# Debug_IO_Board.net
KiCad netlist of a schematic drawn in Altium Designer
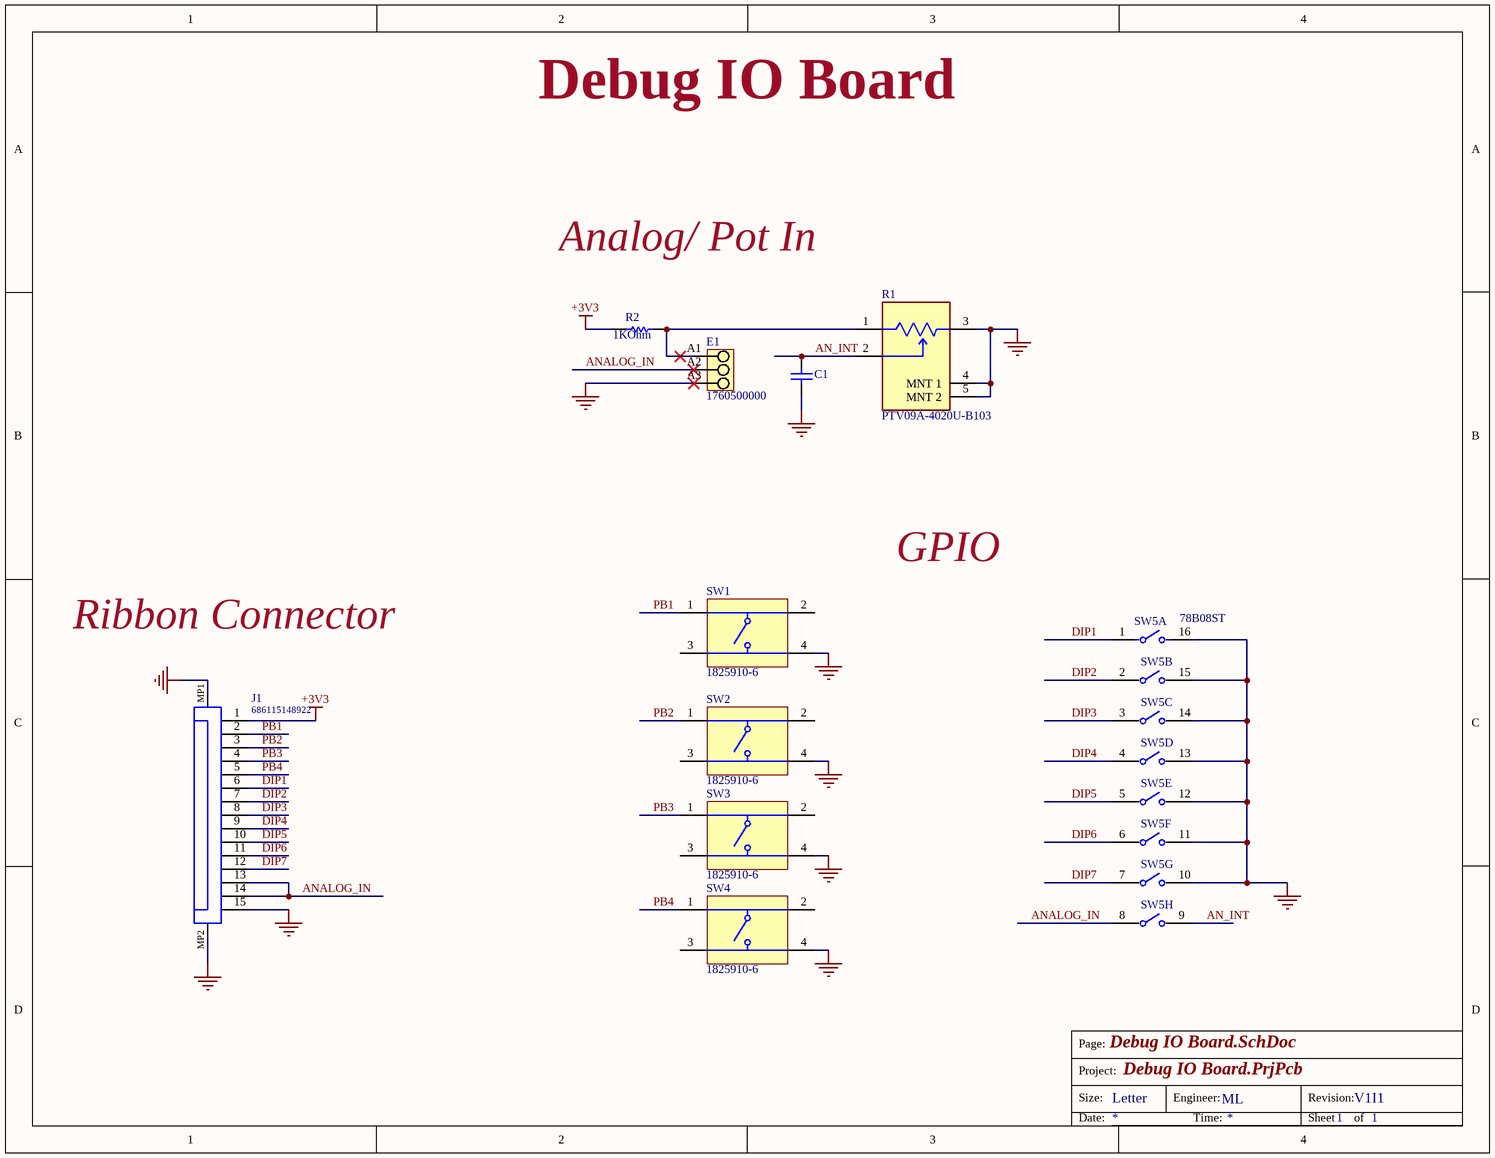
[diagram p0: Debug IO Board.SchDoc]

(export (version "E")
  (design (tool "Eeschema 10.0.6"))
  (components
    (comp (ref "C1")
      (value "C0805C105K4PACTU")
      (footprint "CAPC2013X145X50LL20T25")
      (fields (field (name "MANUFACTURER") "Kemet"))
      (libsource (lib "Altium Content Vault") (part "CAP"))
    )
    (comp (ref "E1")
      (value "1760500000")
      (footprint "PM_5_08_90_03")
      (description "OMNIMATE Signal - series PM")
      (fields (field (name "MANUFACTURER") "Weidmueller"))
      (libsource (lib "Altium Content Vault") (part "Terminal_03_1x03"))
    )
    (comp (ref "J1")
      (value "686115148922")
      (footprint "686115148922")
      (description "SMT ZIF Connectors Hinge Type WR-FPC, Horizontal, Bottom Contact, pitch 1 mm, 15 pins")
      (fields (field (name "MANUFACTURER") "Wurth Elektronik") (field (name "PUBLISHER") "WurthElektronik"))
      (libsource (lib "Altium Content Vault") (part "WE-6861151XXX22-15"))
    )
    (comp (ref "R1")
      (value "PTV09A-4020U-B103")
      (footprint "FP-PTV09A-4-MFG")
      (description "POT 10K OHM 1/20W CARBON LINEAR")
      (fields (field (name "TOLERANCE") "20%") (field (name "MANUFACTURER") "Bourns Inc."))
      (libsource (lib "Altium Content Vault") (part "3454c451b146ec4d4239c7813666f62"))
    )
    (comp (ref "R2")
      (value "RC0805FR-071KL")
      (footprint "RESC2013X60X35ML10T20")
      (description "Chip Resistor, 1 KOhm, +/- 1%, 125 mW, -55 to 155 degC, 0805 (2012 Metric), RoHS, Tape and Reel")
      (fields
        (field (name "RESISTANCE") "1KOhm")
        (field (name "TOLERANCE") "1%")
        (field (name "MANUFACTURER") "Yageo")
      )
      (libsource (lib "Altium Content Vault") (part "RES-2"))
    )
    (comp (ref "SW1")
      (value "1825910-6")
      (footprint "TECO-1825910-6_V")
      (description "Tact Switch, SPST-NO, 0.05 A, -35 to 85 degC, 4-Pin THD, RoHS, Bulk")
      (fields (field (name "MANUFACTURER") "TE Connectivity"))
      (libsource (lib "Altium Content Vault") (part "SW-SPST-4_A"))
    )
    (comp (ref "SW2")
      (value "1825910-6")
      (footprint "TECO-1825910-6_V")
      (description "Tact Switch, SPST-NO, 0.05 A, -35 to 85 degC, 4-Pin THD, RoHS, Bulk")
      (fields (field (name "MANUFACTURER") "TE Connectivity"))
      (libsource (lib "Altium Content Vault") (part "SW-SPST-4_A"))
    )
    (comp (ref "SW3")
      (value "1825910-6")
      (footprint "TECO-1825910-6_V")
      (description "Tact Switch, SPST-NO, 0.05 A, -35 to 85 degC, 4-Pin THD, RoHS, Bulk")
      (fields (field (name "MANUFACTURER") "TE Connectivity"))
      (libsource (lib "Altium Content Vault") (part "SW-SPST-4_A"))
    )
    (comp (ref "SW4")
      (value "1825910-6")
      (footprint "TECO-1825910-6_V")
      (description "Tact Switch, SPST-NO, 0.05 A, -35 to 85 degC, 4-Pin THD, RoHS, Bulk")
      (fields (field (name "MANUFACTURER") "TE Connectivity"))
      (libsource (lib "Altium Content Vault") (part "SW-SPST-4_A"))
    )
    (comp (ref "SW5")
      (value "78B08ST")
      (footprint "FP-78B08ST-MFG")
      (description "SWITCH SLIDE DIP SPST 150MA 30V")
      (fields
        (field (name "MANUFACTURER") "Grayhill")
        (field (name "OCTOPART") "https://octopart.com/78b08st-grayhill-913939")
      )
      (libsource (lib "Altium Content Vault") (part "b1c630a2f26d6f55c46b66680387f8a"))
    )
  )
  (nets
    (net (code "1") (name "+3V3") (class "Default")
      (node (ref "J1") (pin "1") (pinfunction "1_1") (pintype "passive"))
      (node (ref "R2") (pin "1") (pinfunction "1_1") (pintype "passive"))
    )
    (net (code "2") (name "/ANALOG_IN") (class "Default")
      (node (ref "E1") (pin "A2") (pinfunction "A2_A2") (pintype "passive"))
      (node (ref "J1") (pin "13") (pinfunction "13_13") (pintype "passive"))
      (node (ref "J1") (pin "14") (pinfunction "14_14") (pintype "passive"))
      (node (ref "SW5") (pin "8") (pinfunction "8_8") (pintype "passive"))
    )
    (net (code "3") (name "/AN_INT") (class "Default")
      (node (ref "C1") (pin "2") (pinfunction "2_2") (pintype "passive"))
      (node (ref "R1") (pin "2") (pinfunction "2_2") (pintype "passive"))
      (node (ref "SW5") (pin "9") (pinfunction "9_9") (pintype "passive"))
    )
    (net (code "4") (name "/DIP1") (class "Default")
      (node (ref "J1") (pin "6") (pinfunction "6_6") (pintype "passive"))
      (node (ref "SW5") (pin "1") (pinfunction "1_1") (pintype "passive"))
    )
    (net (code "5") (name "/DIP2") (class "Default")
      (node (ref "J1") (pin "7") (pinfunction "7_7") (pintype "passive"))
      (node (ref "SW5") (pin "2") (pinfunction "2_2") (pintype "passive"))
    )
    (net (code "6") (name "/DIP3") (class "Default")
      (node (ref "J1") (pin "8") (pinfunction "8_8") (pintype "passive"))
      (node (ref "SW5") (pin "3") (pinfunction "3_3") (pintype "passive"))
    )
    (net (code "7") (name "/DIP4") (class "Default")
      (node (ref "J1") (pin "9") (pinfunction "9_9") (pintype "passive"))
      (node (ref "SW5") (pin "4") (pinfunction "4_4") (pintype "passive"))
    )
    (net (code "8") (name "/DIP5") (class "Default")
      (node (ref "J1") (pin "10") (pinfunction "10_10") (pintype "passive"))
      (node (ref "SW5") (pin "5") (pinfunction "5_5") (pintype "passive"))
    )
    (net (code "9") (name "/DIP6") (class "Default")
      (node (ref "J1") (pin "11") (pinfunction "11_11") (pintype "passive"))
      (node (ref "SW5") (pin "6") (pinfunction "6_6") (pintype "passive"))
    )
    (net (code "10") (name "/DIP7") (class "Default")
      (node (ref "J1") (pin "12") (pinfunction "12_12") (pintype "passive"))
      (node (ref "SW5") (pin "7") (pinfunction "7_7") (pintype "passive"))
    )
    (net (code "11") (name "/PB1") (class "Default")
      (node (ref "J1") (pin "2") (pinfunction "2_2") (pintype "passive"))
      (node (ref "SW1") (pin "1") (pinfunction "1_1") (pintype "passive"))
    )
    (net (code "12") (name "/PB2") (class "Default")
      (node (ref "J1") (pin "3") (pinfunction "3_3") (pintype "passive"))
      (node (ref "SW2") (pin "1") (pinfunction "1_1") (pintype "passive"))
    )
    (net (code "13") (name "/PB3") (class "Default")
      (node (ref "J1") (pin "4") (pinfunction "4_4") (pintype "passive"))
      (node (ref "SW3") (pin "1") (pinfunction "1_1") (pintype "passive"))
    )
    (net (code "14") (name "/PB4") (class "Default")
      (node (ref "J1") (pin "5") (pinfunction "5_5") (pintype "passive"))
      (node (ref "SW4") (pin "1") (pinfunction "1_1") (pintype "passive"))
    )
    (net (code "15") (name "GND") (class "Default")
      (node (ref "C1") (pin "1") (pinfunction "1_1") (pintype "passive"))
      (node (ref "E1") (pin "A3") (pinfunction "A3_A3") (pintype "passive"))
      (node (ref "J1") (pin "15") (pinfunction "15_15") (pintype "passive"))
      (node (ref "J1") (pin "MP1") (pinfunction "MP1_MP1") (pintype "passive"))
      (node (ref "J1") (pin "MP2") (pinfunction "MP2_MP2") (pintype "passive"))
      (node (ref "R1") (pin "3") (pinfunction "3_3") (pintype "passive"))
      (node (ref "R1") (pin "4") (pinfunction "MNT_1_4") (pintype "passive"))
      (node (ref "R1") (pin "5") (pinfunction "MNT_2_5") (pintype "passive"))
      (node (ref "SW1") (pin "4") (pinfunction "4_4") (pintype "passive"))
      (node (ref "SW2") (pin "4") (pinfunction "4_4") (pintype "passive"))
      (node (ref "SW3") (pin "4") (pinfunction "4_4") (pintype "passive"))
      (node (ref "SW4") (pin "4") (pinfunction "4_4") (pintype "passive"))
      (node (ref "SW5") (pin "10") (pinfunction "10_10") (pintype "passive"))
      (node (ref "SW5") (pin "11") (pinfunction "11_11") (pintype "passive"))
      (node (ref "SW5") (pin "12") (pinfunction "12_12") (pintype "passive"))
      (node (ref "SW5") (pin "13") (pinfunction "13_13") (pintype "passive"))
      (node (ref "SW5") (pin "14") (pinfunction "14_14") (pintype "passive"))
      (node (ref "SW5") (pin "15") (pinfunction "15_15") (pintype "passive"))
      (node (ref "SW5") (pin "16") (pinfunction "16_16") (pintype "passive"))
    )
    (net (code "16") (name "Net-(E1-PadA1)") (class "Default")
      (node (ref "E1") (pin "A1") (pinfunction "A1_A1") (pintype "passive"))
      (node (ref "R1") (pin "1") (pinfunction "1_1") (pintype "passive"))
      (node (ref "R2") (pin "2") (pinfunction "2_2") (pintype "passive"))
    )
    (net (code "17") (name "unconnected-(SW1-Pad2)") (class "Default")
      (node (ref "SW1") (pin "2") (pinfunction "2_2") (pintype "passive"))
    )
    (net (code "18") (name "unconnected-(SW1-Pad3)") (class "Default")
      (node (ref "SW1") (pin "3") (pinfunction "3_3") (pintype "passive"))
    )
    (net (code "19") (name "unconnected-(SW2-Pad2)") (class "Default")
      (node (ref "SW2") (pin "2") (pinfunction "2_2") (pintype "passive"))
    )
    (net (code "20") (name "unconnected-(SW2-Pad3)") (class "Default")
      (node (ref "SW2") (pin "3") (pinfunction "3_3") (pintype "passive"))
    )
    (net (code "21") (name "unconnected-(SW3-Pad2)") (class "Default")
      (node (ref "SW3") (pin "2") (pinfunction "2_2") (pintype "passive"))
    )
    (net (code "22") (name "unconnected-(SW3-Pad3)") (class "Default")
      (node (ref "SW3") (pin "3") (pinfunction "3_3") (pintype "passive"))
    )
    (net (code "23") (name "unconnected-(SW4-Pad2)") (class "Default")
      (node (ref "SW4") (pin "2") (pinfunction "2_2") (pintype "passive"))
    )
    (net (code "24") (name "unconnected-(SW4-Pad3)") (class "Default")
      (node (ref "SW4") (pin "3") (pinfunction "3_3") (pintype "passive"))
    )
  )
)
